# CH32M030G8R7-R0.net
KiCad netlist of a schematic drawn in Altium Designer
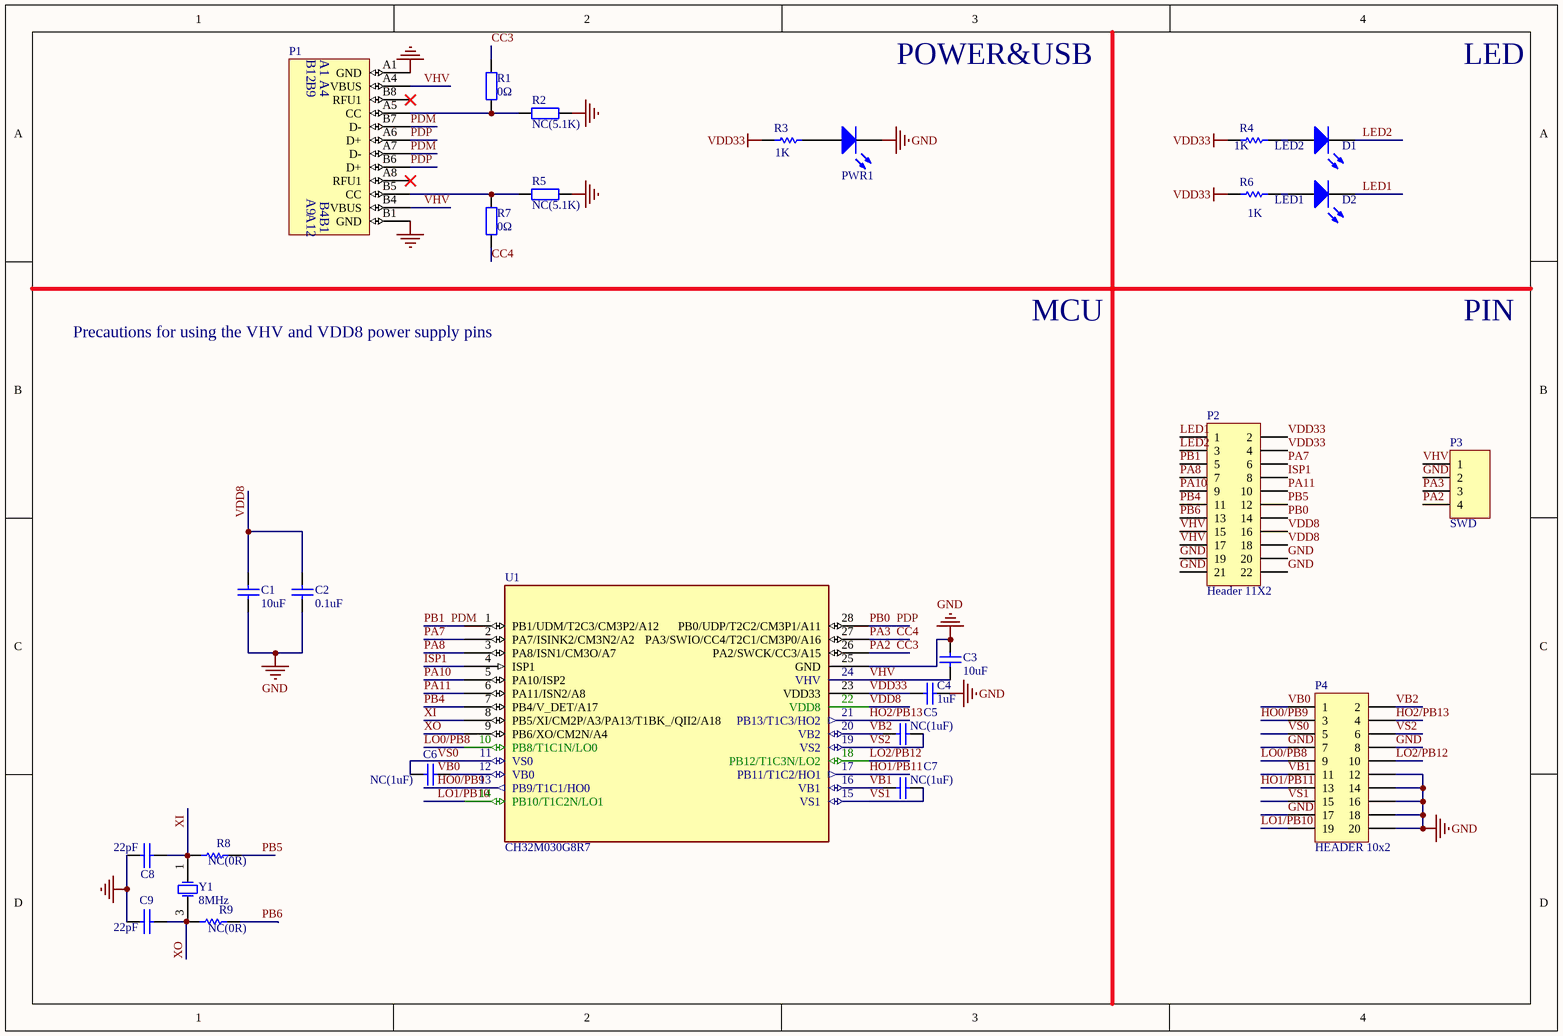
[diagram p0: CH32M030G8R7-R0.SchDoc]

(export (version "E")
  (design (tool "Eeschema 10.0.6"))
  (components
    (comp (ref "C1")
      (value "10uF")
      (footprint "0603_C")
      (description "Capacitor")
      (fields (field (name "PUBLISHER") "Altium Limited"))
      (libsource (lib "*") (part "Cap"))
    )
    (comp (ref "C2")
      (value "0.1uF")
      (footprint "0603_C")
      (description "Capacitor")
      (fields (field (name "PUBLISHER") "Altium Limited"))
      (libsource (lib "*") (part "Cap"))
    )
    (comp (ref "C3")
      (value "10uF")
      (footprint "0603_C")
      (description "Capacitor")
      (fields (field (name "PUBLISHER") "Altium Limited"))
      (libsource (lib "*") (part "Cap"))
    )
    (comp (ref "C4")
      (value "1uF")
      (footprint "0603_C")
      (description "Capacitor")
      (fields (field (name "PUBLISHER") "Altium Limited"))
      (libsource (lib "*") (part "Cap"))
    )
    (comp (ref "C5")
      (value "NC(1uF)")
      (footprint "0603_C")
      (description "Capacitor")
      (fields (field (name "PUBLISHER") "Altium Limited"))
      (libsource (lib "*") (part "Cap"))
    )
    (comp (ref "C6")
      (value "NC(1uF)")
      (footprint "0603_C")
      (description "Capacitor")
      (fields (field (name "PUBLISHER") "Altium Limited"))
      (libsource (lib "*") (part "Cap"))
    )
    (comp (ref "C7")
      (value "NC(1uF)")
      (footprint "0603_C")
      (description "Capacitor")
      (fields (field (name "PUBLISHER") "Altium Limited"))
      (libsource (lib "*") (part "Cap"))
    )
    (comp (ref "C8")
      (value "22pF")
      (footprint "0603_C")
      (description "Capacitor")
      (libsource (lib "*") (part "CAP"))
    )
    (comp (ref "C9")
      (value "22pF")
      (footprint "0603_C")
      (description "Capacitor")
      (libsource (lib "*") (part "CAP"))
    )
    (comp (ref "D1")
      (value "LED2")
      (footprint "0603+")
      (description "Typical INFRARED GaAs LED")
      (fields (field (name "PUBLISHER") "Altium Limited"))
      (libsource (lib "*") (part "LED0"))
    )
    (comp (ref "D2")
      (value "LED1")
      (footprint "0603+")
      (description "Typical INFRARED GaAs LED")
      (fields (field (name "PUBLISHER") "Altium Limited"))
      (libsource (lib "*") (part "LED0"))
    )
    (comp (ref "P1")
      (value "TYPE-C")
      (footprint "TYPE-C-Receptacle-2.0")
      (libsource (lib "*") (part "TYPE-C1"))
    )
    (comp (ref "P2")
      (value "Header 11X2")
      (footprint "IDC22-2.54mm")
      (description "Header, 11-Pin, Dual row")
      (fields (field (name "PUBLISHER") "Altium Limited"))
      (libsource (lib "Miscellaneous Connectors") (part "Header 11X2"))
    )
    (comp (ref "P3")
      (value "SWD")
      (footprint "SIP4-2.54mm")
      (description "Header, 4-Pin")
      (libsource (lib "wch_sch_others") (part "HEADER 4"))
    )
    (comp (ref "P4")
      (value "HEADER 10x2")
      (footprint "MYPCB:IDC20-2.54MM")
      (description "Header, 10-Pin, Dual row")
      (libsource (lib "wch_sch_others") (part "HEADER 10x2"))
    )
    (comp (ref "PWR1")
      (value "POWER  red")
      (footprint "0603+")
      (description "Typical INFRARED GaAs LED")
      (fields (field (name "PUBLISHER") "Altium Limited"))
      (libsource (lib "*") (part "LED0"))
    )
    (comp (ref "R1")
      (value "0Ω")
      (footprint "0603")
      (description "Resistor")
      (libsource (lib "") (part "Res2_1"))
    )
    (comp (ref "R2")
      (value "NC(5.1K)")
      (footprint "0603")
      (description "Resistor")
      (libsource (lib "Miscellaneous Devices") (part "Res2"))
    )
    (comp (ref "R3")
      (value "1K")
      (footprint "0603")
      (description "Semiconductor Resistor")
      (fields (field (name "PUBLISHER") "Altium Limited"))
      (libsource (lib "*") (part "Res Semi"))
    )
    (comp (ref "R4")
      (value "1K")
      (footprint "0603")
      (description "Semiconductor Resistor")
      (fields (field (name "PUBLISHER") "Altium Limited"))
      (libsource (lib "*") (part "Res Semi"))
    )
    (comp (ref "R5")
      (value "NC(5.1K)")
      (footprint "0603")
      (description "Resistor")
      (libsource (lib "Miscellaneous Devices") (part "Res2"))
    )
    (comp (ref "R6")
      (value "1K")
      (footprint "0603")
      (description "Semiconductor Resistor")
      (fields (field (name "PUBLISHER") "Altium Limited"))
      (libsource (lib "*") (part "Res Semi"))
    )
    (comp (ref "R7")
      (value "0Ω")
      (footprint "0603")
      (description "Resistor")
      (libsource (lib "") (part "Res2_1"))
    )
    (comp (ref "R8")
      (value "NC(0R)")
      (footprint "0603")
      (description "Semiconductor Resistor")
      (fields (field (name "PUBLISHER") "Altium Limited"))
      (libsource (lib "*") (part "Res Semi"))
    )
    (comp (ref "R9")
      (value "NC(0R)")
      (footprint "0603")
      (description "Semiconductor Resistor")
      (fields (field (name "PUBLISHER") "Altium Limited"))
      (libsource (lib "*") (part "Res Semi"))
    )
    (comp (ref "U1")
      (value "CH32M030G8R7")
      (footprint "QSOP28")
      (description "RISC-V MCU, 72MHz, USB, Type-C/PD, OPA, CMP, 28V gate driver")
      (libsource (lib "CHXXX") (part "CH32M030G8R7"))
    )
    (comp (ref "Y1")
      (value "8MHz")
      (footprint "XT3225")
      (description "Crystal Oscillator")
      (fields (field (name "PUBLISHER") "Altium Limited"))
      (libsource (lib "*") (part "XTAL"))
    )
  )
  (nets
    (net (code "1") (name "/CC3") (class "Default")
      (node (ref "P3") (pin "4") (pinfunction "4_4") (pintype "passive"))
      (node (ref "R1") (pin "2") (pinfunction "2_2") (pintype "passive"))
      (node (ref "U1") (pin "26") (pinfunction "PA2/SWCK/CC3/A15_26") (pintype "bidirectional"))
    )
    (net (code "2") (name "/CC4") (class "Default")
      (node (ref "P3") (pin "3") (pinfunction "3_3") (pintype "passive"))
      (node (ref "R7") (pin "1") (pinfunction "1_1") (pintype "passive"))
      (node (ref "U1") (pin "27") (pinfunction "PA3/SWIO/CC4/T2C1/CM3P0/A16_27") (pintype "bidirectional"))
    )
    (net (code "3") (name "/HO0{slash}PB9") (class "Default")
      (node (ref "P4") (pin "3") (pinfunction "3_3") (pintype "passive"))
      (node (ref "U1") (pin "13") (pinfunction "PB9/T1C1/HO0_13") (pintype "output"))
    )
    (net (code "4") (name "/HO1{slash}PB11") (class "Default")
      (node (ref "P4") (pin "13") (pinfunction "13_13") (pintype "passive"))
      (node (ref "U1") (pin "17") (pinfunction "PB11/T1C2/HO1_17") (pintype "output"))
    )
    (net (code "5") (name "/HO2{slash}PB13") (class "Default")
      (node (ref "P4") (pin "4") (pinfunction "4_4") (pintype "passive"))
      (node (ref "U1") (pin "21") (pinfunction "PB13/T1C3/HO2_21") (pintype "output"))
    )
    (net (code "6") (name "/ISP1") (class "Default")
      (node (ref "P2") (pin "8") (pinfunction "8_8") (pintype "passive"))
      (node (ref "U1") (pin "4") (pinfunction "ISP1_4") (pintype "input"))
    )
    (net (code "7") (name "/LED1") (class "Default")
      (node (ref "D2") (pin "2") (pinfunction "K_2") (pintype "passive"))
      (node (ref "P2") (pin "1") (pinfunction "1_1") (pintype "passive"))
    )
    (net (code "8") (name "/LED2") (class "Default")
      (node (ref "D1") (pin "2") (pinfunction "K_2") (pintype "passive"))
      (node (ref "P2") (pin "3") (pinfunction "3_3") (pintype "passive"))
    )
    (net (code "9") (name "/LO0{slash}PB8") (class "Default")
      (node (ref "P4") (pin "9") (pinfunction "9_9") (pintype "passive"))
      (node (ref "U1") (pin "10") (pinfunction "PB8/T1C1N/LO0_10") (pintype "bidirectional"))
    )
    (net (code "10") (name "/LO1{slash}PB10") (class "Default")
      (node (ref "P4") (pin "19") (pinfunction "19_19") (pintype "passive"))
      (node (ref "U1") (pin "14") (pinfunction "PB10/T1C2N/LO1_14") (pintype "bidirectional"))
    )
    (net (code "11") (name "/LO2{slash}PB12") (class "Default")
      (node (ref "P4") (pin "10") (pinfunction "10_10") (pintype "passive"))
      (node (ref "U1") (pin "18") (pinfunction "PB12/T1C3N/LO2_18") (pintype "bidirectional"))
    )
    (net (code "12") (name "/PA7") (class "Default")
      (node (ref "P2") (pin "6") (pinfunction "6_6") (pintype "passive"))
      (node (ref "U1") (pin "2") (pinfunction "PA7/ISINK2/CM3N2/A2_2") (pintype "bidirectional"))
    )
    (net (code "13") (name "/PA8") (class "Default")
      (node (ref "P2") (pin "7") (pinfunction "7_7") (pintype "passive"))
      (node (ref "U1") (pin "3") (pinfunction "PA8/ISN1/CM3O/A7_3") (pintype "bidirectional"))
    )
    (net (code "14") (name "/PA10") (class "Default")
      (node (ref "P2") (pin "9") (pinfunction "9_9") (pintype "passive"))
      (node (ref "U1") (pin "5") (pinfunction "PA10/ISP2_5") (pintype "bidirectional"))
    )
    (net (code "15") (name "/PA11") (class "Default")
      (node (ref "P2") (pin "10") (pinfunction "10_10") (pintype "passive"))
      (node (ref "U1") (pin "6") (pinfunction "PA11/ISN2/A8_6") (pintype "bidirectional"))
    )
    (net (code "16") (name "/PB0") (class "Default")
      (node (ref "P1") (pin "A6") (pinfunction "D+_A6") (pintype "bidirectional"))
      (node (ref "P1") (pin "B6") (pinfunction "D+_B6") (pintype "bidirectional"))
      (node (ref "P2") (pin "14") (pinfunction "14_14") (pintype "passive"))
      (node (ref "U1") (pin "28") (pinfunction "PB0/UDP/T2C2/CM3P1/A11_28") (pintype "bidirectional"))
    )
    (net (code "17") (name "/PB1") (class "Default")
      (node (ref "P1") (pin "A7") (pinfunction "D-_A7") (pintype "bidirectional"))
      (node (ref "P1") (pin "B7") (pinfunction "D-_B7") (pintype "bidirectional"))
      (node (ref "P2") (pin "5") (pinfunction "5_5") (pintype "passive"))
      (node (ref "U1") (pin "1") (pinfunction "PB1/UDM/T2C3/CM3P2/A12_1") (pintype "bidirectional"))
    )
    (net (code "18") (name "/PB4") (class "Default")
      (node (ref "P2") (pin "11") (pinfunction "11_11") (pintype "passive"))
      (node (ref "U1") (pin "7") (pinfunction "PB4/V_DET/A17_7") (pintype "bidirectional"))
    )
    (net (code "19") (name "/PB5") (class "Default")
      (node (ref "P2") (pin "12") (pinfunction "12_12") (pintype "passive"))
      (node (ref "R8") (pin "2") (pinfunction "2_2") (pintype "passive"))
    )
    (net (code "20") (name "/PB6") (class "Default")
      (node (ref "P2") (pin "13") (pinfunction "13_13") (pintype "passive"))
      (node (ref "R9") (pin "2") (pinfunction "2_2") (pintype "passive"))
    )
    (net (code "21") (name "/VB0") (class "Default")
      (node (ref "P4") (pin "1") (pinfunction "1_1") (pintype "passive"))
    )
    (net (code "22") (name "/VB1") (class "Default")
      (node (ref "C7") (pin "2") (pinfunction "2_2") (pintype "passive"))
      (node (ref "P4") (pin "11") (pinfunction "11_11") (pintype "passive"))
      (node (ref "U1") (pin "16") (pinfunction "VB1_16") (pintype "bidirectional"))
    )
    (net (code "23") (name "/VB2") (class "Default")
      (node (ref "C5") (pin "2") (pinfunction "2_2") (pintype "passive"))
      (node (ref "P4") (pin "2") (pinfunction "2_2") (pintype "passive"))
      (node (ref "U1") (pin "20") (pinfunction "VB2_20") (pintype "bidirectional"))
    )
    (net (code "24") (name "/VDD8") (class "Default")
      (node (ref "C1") (pin "2") (pinfunction "2_2") (pintype "passive"))
      (node (ref "C2") (pin "2") (pinfunction "2_2") (pintype "passive"))
      (node (ref "P2") (pin "16") (pinfunction "16_16") (pintype "passive"))
      (node (ref "P2") (pin "18") (pinfunction "18_18") (pintype "passive"))
      (node (ref "U1") (pin "22") (pinfunction "VDD8_22") (pintype "power_in"))
    )
    (net (code "25") (name "/VHV") (class "Default")
      (node (ref "C3") (pin "2") (pinfunction "2_2") (pintype "passive"))
      (node (ref "P1") (pin "A4") (pinfunction "VBUS_A4") (pintype "bidirectional"))
      (node (ref "P1") (pin "B4") (pinfunction "VBUS_B4") (pintype "bidirectional"))
      (node (ref "P2") (pin "15") (pinfunction "15_15") (pintype "passive"))
      (node (ref "P2") (pin "17") (pinfunction "17_17") (pintype "passive"))
      (node (ref "P3") (pin "1") (pinfunction "1_1") (pintype "passive"))
      (node (ref "U1") (pin "24") (pinfunction "VHV_24") (pintype "power_in"))
    )
    (net (code "26") (name "/VS0") (class "Default")
      (node (ref "C6") (pin "1") (pinfunction "1_1") (pintype "passive"))
      (node (ref "P4") (pin "5") (pinfunction "5_5") (pintype "passive"))
      (node (ref "U1") (pin "11") (pinfunction "VS0_11") (pintype "bidirectional"))
    )
    (net (code "27") (name "/VS1") (class "Default")
      (node (ref "C7") (pin "1") (pinfunction "1_1") (pintype "passive"))
      (node (ref "P4") (pin "15") (pinfunction "15_15") (pintype "passive"))
      (node (ref "U1") (pin "15") (pinfunction "VS1_15") (pintype "bidirectional"))
    )
    (net (code "28") (name "/VS2") (class "Default")
      (node (ref "C5") (pin "1") (pinfunction "1_1") (pintype "passive"))
      (node (ref "P4") (pin "6") (pinfunction "6_6") (pintype "passive"))
      (node (ref "U1") (pin "19") (pinfunction "VS2_19") (pintype "bidirectional"))
    )
    (net (code "29") (name "/XI") (class "Default")
      (node (ref "C8") (pin "2") (pinfunction "2_2") (pintype "passive"))
      (node (ref "R8") (pin "1") (pinfunction "1_1") (pintype "passive"))
      (node (ref "U1") (pin "8") (pinfunction "PB5/XI/CM2P/A3/PA13/T1BK_/QII2/A18_8") (pintype "bidirectional"))
      (node (ref "Y1") (pin "1") (pinfunction "OSC1_1") (pintype "passive"))
    )
    (net (code "30") (name "/XO") (class "Default")
      (node (ref "C9") (pin "2") (pinfunction "2_2") (pintype "passive"))
      (node (ref "R9") (pin "1") (pinfunction "1_1") (pintype "passive"))
      (node (ref "U1") (pin "9") (pinfunction "PB6/XO/CM2N/A4_9") (pintype "bidirectional"))
    )
    (net (code "31") (name "GND") (class "Default")
      (node (ref "C1") (pin "1") (pinfunction "1_1") (pintype "passive"))
      (node (ref "C2") (pin "1") (pinfunction "1_1") (pintype "passive"))
      (node (ref "C3") (pin "1") (pinfunction "1_1") (pintype "passive"))
      (node (ref "C4") (pin "1") (pinfunction "1_1") (pintype "passive"))
      (node (ref "C8") (pin "1") (pinfunction "1_1") (pintype "passive"))
      (node (ref "C9") (pin "1") (pinfunction "1_1") (pintype "passive"))
      (node (ref "P1") (pin "A1") (pinfunction "GND_A1") (pintype "bidirectional"))
      (node (ref "P1") (pin "B1") (pinfunction "GND_B1") (pintype "bidirectional"))
      (node (ref "P2") (pin "19") (pinfunction "19_19") (pintype "passive"))
      (node (ref "P2") (pin "20") (pinfunction "20_20") (pintype "passive"))
      (node (ref "P2") (pin "21") (pinfunction "21_21") (pintype "passive"))
      (node (ref "P2") (pin "22") (pinfunction "22_22") (pintype "passive"))
      (node (ref "P3") (pin "2") (pinfunction "2_2") (pintype "passive"))
      (node (ref "P4") (pin "12") (pinfunction "12_12") (pintype "passive"))
      (node (ref "P4") (pin "14") (pinfunction "14_14") (pintype "passive"))
      (node (ref "P4") (pin "16") (pinfunction "16_16") (pintype "passive"))
      (node (ref "P4") (pin "17") (pinfunction "17_17") (pintype "passive"))
      (node (ref "P4") (pin "18") (pinfunction "18_18") (pintype "passive"))
      (node (ref "P4") (pin "20") (pinfunction "20_20") (pintype "passive"))
      (node (ref "P4") (pin "7") (pinfunction "7_7") (pintype "passive"))
      (node (ref "P4") (pin "8") (pinfunction "8_8") (pintype "passive"))
      (node (ref "PWR1") (pin "2") (pinfunction "K_2") (pintype "passive"))
      (node (ref "R2") (pin "2") (pinfunction "2_2") (pintype "passive"))
      (node (ref "R5") (pin "2") (pinfunction "2_2") (pintype "passive"))
      (node (ref "U1") (pin "25") (pinfunction "GND_25") (pintype "power_in"))
    )
    (net (code "32") (name "Net-(D1-A)") (class "Default")
      (node (ref "D1") (pin "1") (pinfunction "A_1") (pintype "passive"))
      (node (ref "R4") (pin "2") (pinfunction "2_2") (pintype "passive"))
    )
    (net (code "33") (name "Net-(D2-A)") (class "Default")
      (node (ref "D2") (pin "1") (pinfunction "A_1") (pintype "passive"))
      (node (ref "R6") (pin "2") (pinfunction "2_2") (pintype "passive"))
    )
    (net (code "34") (name "Net-(P1-CC-PadA5)") (class "Default")
      (node (ref "P1") (pin "A5") (pinfunction "CC_A5") (pintype "bidirectional"))
      (node (ref "R1") (pin "1") (pinfunction "1_1") (pintype "passive"))
      (node (ref "R2") (pin "1") (pinfunction "1_1") (pintype "passive"))
    )
    (net (code "35") (name "Net-(P1-CC-PadB5)") (class "Default")
      (node (ref "P1") (pin "B5") (pinfunction "CC_B5") (pintype "bidirectional"))
      (node (ref "R5") (pin "1") (pinfunction "1_1") (pintype "passive"))
      (node (ref "R7") (pin "2") (pinfunction "2_2") (pintype "passive"))
    )
    (net (code "36") (name "Net-(PWR1-A)") (class "Default")
      (node (ref "PWR1") (pin "1") (pinfunction "A_1") (pintype "passive"))
      (node (ref "R3") (pin "1") (pinfunction "1_1") (pintype "passive"))
    )
    (net (code "37") (name "Net-(U1-VB0)") (class "Default")
      (node (ref "C6") (pin "2") (pinfunction "2_2") (pintype "passive"))
      (node (ref "U1") (pin "12") (pinfunction "VB0_12") (pintype "bidirectional"))
    )
    (net (code "38") (name "VDD33") (class "Default")
      (node (ref "C4") (pin "2") (pinfunction "2_2") (pintype "passive"))
      (node (ref "P2") (pin "2") (pinfunction "2_2") (pintype "passive"))
      (node (ref "P2") (pin "4") (pinfunction "4_4") (pintype "passive"))
      (node (ref "R3") (pin "2") (pinfunction "2_2") (pintype "passive"))
      (node (ref "R4") (pin "1") (pinfunction "1_1") (pintype "passive"))
      (node (ref "R6") (pin "1") (pinfunction "1_1") (pintype "passive"))
      (node (ref "U1") (pin "23") (pinfunction "VDD33_23") (pintype "power_in"))
    )
    (net (code "39") (name "unconnected-(P1-RFU1-PadA8)") (class "Default")
      (node (ref "P1") (pin "A8") (pinfunction "RFU1_A8") (pintype "bidirectional+no_connect"))
    )
    (net (code "40") (name "unconnected-(P1-RFU1-PadB8)") (class "Default")
      (node (ref "P1") (pin "B8") (pinfunction "RFU1_B8") (pintype "bidirectional+no_connect"))
    )
    (net (code "41") (name "unconnected-(Y1-OSC2-Pad3)") (class "Default")
      (node (ref "Y1") (pin "3") (pinfunction "OSC2_3") (pintype "passive"))
    )
  )
)
